# controller_schematic.net
KiCad netlist of a schematic drawn in EasyEDA
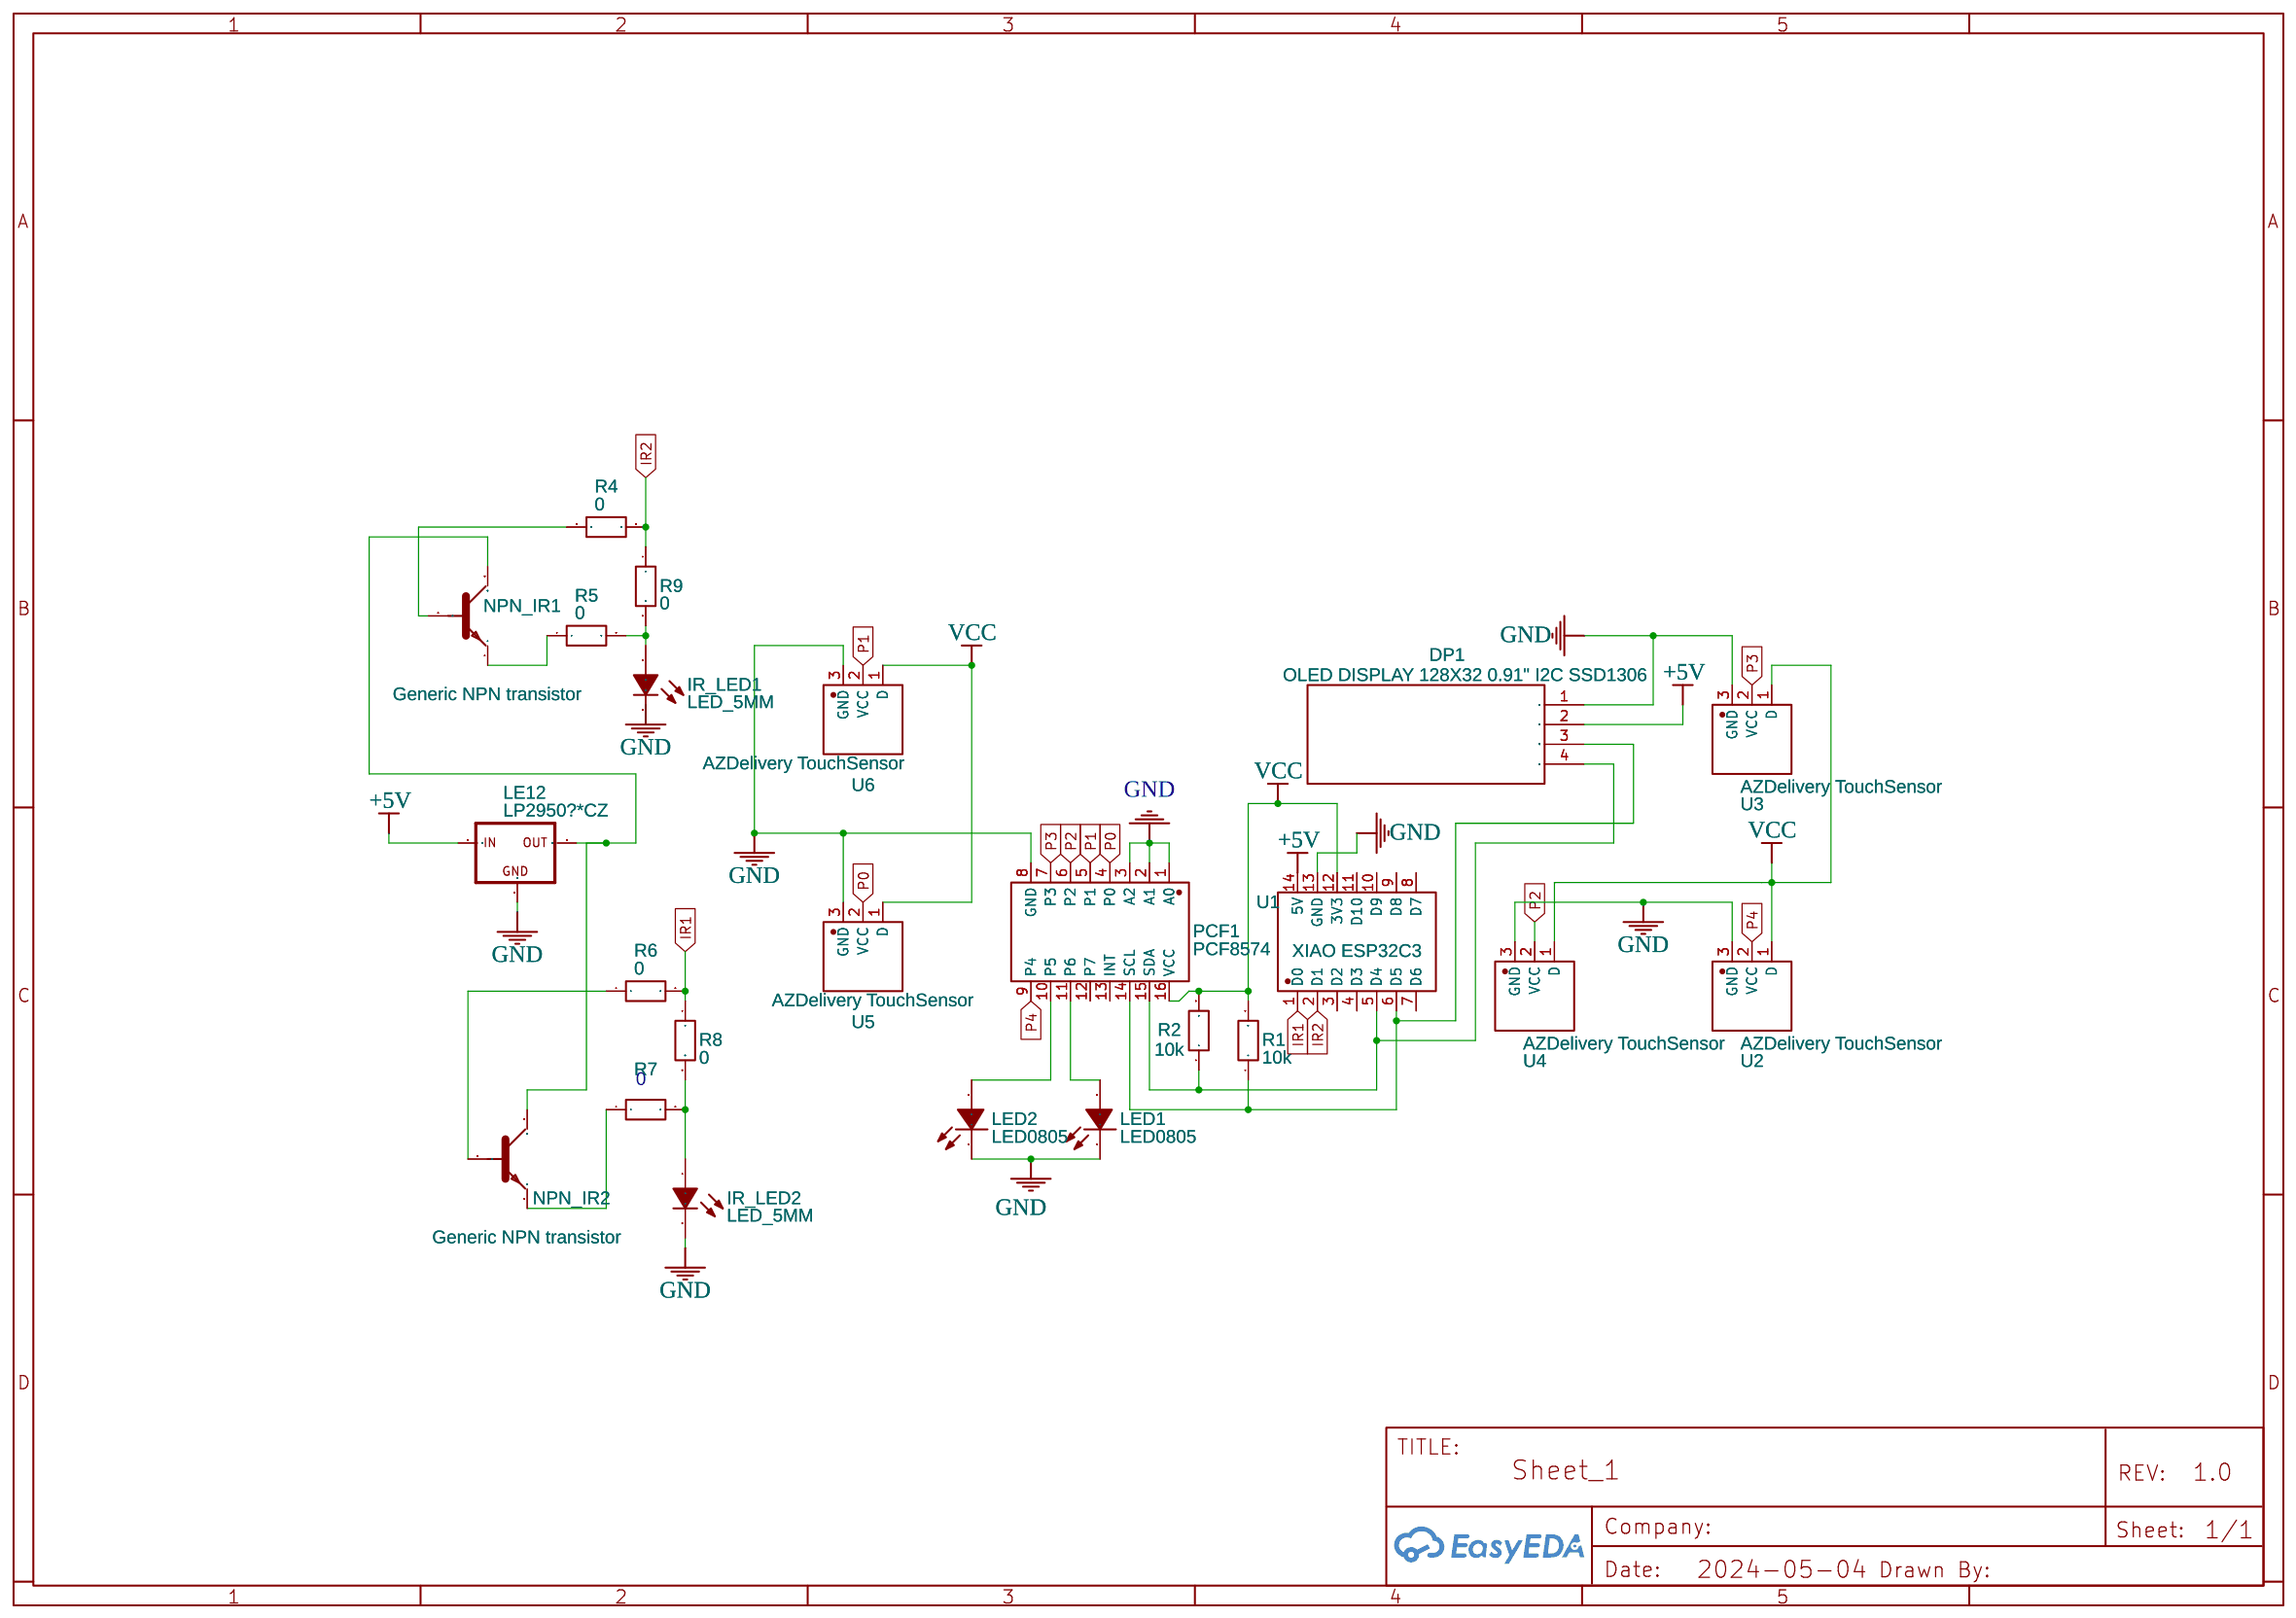
[diagram p0: schematic sheet]

(export (version "E")
  (design (tool "Eeschema 10.0.6"))
  (components
    (comp (ref "DP1")
      (value "OLED DISPLAY 128X32 0.91\" I2C SSD1306")
      (libsource (lib "") (part "OLED DISPLAY 128X32 0.91{dblquote} I2C SSD1306"))
    )
    (comp (ref "IR_LED1") (value "LED_5MM") (libsource (lib "") (part "LED_5MM")))
    (comp (ref "IR_LED2") (value "LED_5MM") (libsource (lib "") (part "LED_5MM")))
    (comp (ref "LE12") (value "LP2950?*CZ") (libsource (lib "") (part "LP2950?*CZ")))
    (comp (ref "LED1")
      (value "LED0805")
      (fields (field (name "Manufacturer Part") "led0805"))
      (libsource (lib "") (part "LED0805"))
    )
    (comp (ref "LED2")
      (value "LED0805")
      (fields (field (name "Manufacturer Part") "led0805"))
      (libsource (lib "") (part "LED0805"))
    )
    (comp (ref "NPN_IR1")
      (value "Generic NPN transistor")
      (fields
        (field (name "Manufacturer Part") "PN2484 PBFREE")
        (field (name "Manufacturer") "Central Semiconductor")
      )
      (libsource (lib "") (part "Generic NPN transistor"))
    )
    (comp (ref "NPN_IR2")
      (value "Generic NPN transistor")
      (fields
        (field (name "Manufacturer Part") "PN2484 PBFREE")
        (field (name "Manufacturer") "Central Semiconductor")
      )
      (libsource (lib "") (part "Generic NPN transistor"))
    )
    (comp (ref "PCF1") (value "PCF8574") (libsource (lib "") (part "PCF8574")))
    (comp (ref "R1") (value "10k") (libsource (lib "") (part "R_0603_EU")))
    (comp (ref "R2") (value "10k") (libsource (lib "") (part "R_0603_EU")))
    (comp (ref "R4") (value "0") (libsource (lib "") (part "R_0603_EU_1")))
    (comp (ref "R5") (value "0") (libsource (lib "") (part "R_0603_EU_1")))
    (comp (ref "R6") (value "0") (libsource (lib "") (part "R_0603_EU_1")))
    (comp (ref "R7") (value "0") (libsource (lib "") (part "R_0603_EU_1")))
    (comp (ref "R8") (value "0") (libsource (lib "") (part "R_0603_EU_2")))
    (comp (ref "R9") (value "0") (libsource (lib "") (part "R_0603_EU_2")))
    (comp (ref "U1") (value "XIAO ESP32C3") (libsource (lib "") (part "XIAO ESP32C3")))
    (comp (ref "U2")
      (value "AZDelivery TouchSensor")
      (fields
        (field (name "Manufacturer Part") "ZJY096S0700BG01蓝色")
        (field (name "Manufacturer") "AZDelivery")
      )
      (libsource (lib "") (part "AZDelivery TouchSensor"))
    )
    (comp (ref "U3")
      (value "AZDelivery TouchSensor")
      (fields
        (field (name "Manufacturer Part") "ZJY096S0700BG01蓝色")
        (field (name "Manufacturer") "AZDelivery")
      )
      (libsource (lib "") (part "AZDelivery TouchSensor"))
    )
    (comp (ref "U4")
      (value "AZDelivery TouchSensor")
      (fields
        (field (name "Manufacturer Part") "ZJY096S0700BG01蓝色")
        (field (name "Manufacturer") "AZDelivery")
      )
      (libsource (lib "") (part "AZDelivery TouchSensor"))
    )
    (comp (ref "U5")
      (value "AZDelivery TouchSensor")
      (fields
        (field (name "Manufacturer Part") "ZJY096S0700BG01蓝色")
        (field (name "Manufacturer") "AZDelivery")
      )
      (libsource (lib "") (part "AZDelivery TouchSensor"))
    )
    (comp (ref "U6")
      (value "AZDelivery TouchSensor")
      (fields
        (field (name "Manufacturer Part") "ZJY096S0700BG01蓝色")
        (field (name "Manufacturer") "AZDelivery")
      )
      (libsource (lib "") (part "AZDelivery TouchSensor"))
    )
  )
  (nets
    (net (code "1") (name "+5V") (class "Default")
      (node (ref "DP1") (pin "2") (pinfunction "VCC_2") (pintype "passive"))
      (node (ref "LE12") (pin "3") (pinfunction "IN_3") (pintype "bidirectional"))
      (node (ref "U1") (pin "14") (pinfunction "5V_14") (pintype "unspecified"))
    )
    (net (code "2") (name "GND") (class "Default")
      (node (ref "DP1") (pin "1") (pinfunction "GND_1") (pintype "passive"))
      (node (ref "IR_LED1") (pin "2") (pinfunction "K_2") (pintype "input"))
      (node (ref "IR_LED2") (pin "2") (pinfunction "K_2") (pintype "input"))
      (node (ref "LE12") (pin "2") (pinfunction "GND_2") (pintype "bidirectional"))
      (node (ref "LED1") (pin "1") (pinfunction "-_1") (pintype "unspecified"))
      (node (ref "LED2") (pin "1") (pinfunction "-_1") (pintype "unspecified"))
      (node (ref "PCF1") (pin "1") (pinfunction "A0_1") (pintype "unspecified"))
      (node (ref "PCF1") (pin "2") (pinfunction "A1_2") (pintype "unspecified"))
      (node (ref "PCF1") (pin "3") (pinfunction "A2_3") (pintype "unspecified"))
      (node (ref "PCF1") (pin "8") (pinfunction "GND_8") (pintype "unspecified"))
      (node (ref "U1") (pin "13") (pinfunction "GND_13") (pintype "unspecified"))
      (node (ref "U2") (pin "3") (pinfunction "GND_3") (pintype "unspecified"))
      (node (ref "U3") (pin "3") (pinfunction "GND_3") (pintype "unspecified"))
      (node (ref "U4") (pin "3") (pinfunction "GND_3") (pintype "unspecified"))
      (node (ref "U5") (pin "3") (pinfunction "GND_3") (pintype "unspecified"))
      (node (ref "U6") (pin "3") (pinfunction "GND_3") (pintype "unspecified"))
    )
    (net (code "3") (name "IR1") (class "Default")
      (node (ref "R6") (pin "2") (pinfunction "2_2") (pintype "unspecified"))
      (node (ref "R8") (pin "1") (pinfunction "1_1") (pintype "unspecified"))
      (node (ref "U1") (pin "1") (pinfunction "D0_1") (pintype "unspecified"))
    )
    (net (code "4") (name "IR2") (class "Default")
      (node (ref "R4") (pin "2") (pinfunction "2_2") (pintype "unspecified"))
      (node (ref "R9") (pin "1") (pinfunction "1_1") (pintype "unspecified"))
      (node (ref "U1") (pin "2") (pinfunction "D1_2") (pintype "unspecified"))
    )
    (net (code "5") (name "Net-(DP1-SCL)") (class "Default")
      (node (ref "DP1") (pin "3") (pinfunction "SCL_3") (pintype "input"))
      (node (ref "PCF1") (pin "14") (pinfunction "SCL_14") (pintype "unspecified"))
      (node (ref "R1") (pin "1") (pinfunction "1_1") (pintype "unspecified"))
      (node (ref "U1") (pin "6") (pinfunction "D5_6") (pintype "unspecified"))
    )
    (net (code "6") (name "Net-(DP1-SDA)") (class "Default")
      (node (ref "DP1") (pin "4") (pinfunction "SDA_4") (pintype "input"))
      (node (ref "PCF1") (pin "15") (pinfunction "SDA_15") (pintype "unspecified"))
      (node (ref "R2") (pin "1") (pinfunction "1_1") (pintype "unspecified"))
      (node (ref "U1") (pin "5") (pinfunction "D4_5") (pintype "unspecified"))
    )
    (net (code "7") (name "Net-(IR_LED1-A)") (class "Default")
      (node (ref "IR_LED1") (pin "1") (pinfunction "A_1") (pintype "input"))
      (node (ref "R5") (pin "2") (pinfunction "2_2") (pintype "unspecified"))
      (node (ref "R9") (pin "2") (pinfunction "2_2") (pintype "unspecified"))
    )
    (net (code "8") (name "Net-(IR_LED2-A)") (class "Default")
      (node (ref "IR_LED2") (pin "1") (pinfunction "A_1") (pintype "input"))
      (node (ref "R7") (pin "2") (pinfunction "2_2") (pintype "unspecified"))
      (node (ref "R8") (pin "2") (pinfunction "2_2") (pintype "unspecified"))
    )
    (net (code "9") (name "Net-(LE12-OUT)") (class "Default")
      (node (ref "LE12") (pin "1") (pinfunction "OUT_1") (pintype "bidirectional"))
      (node (ref "NPN_IR1") (pin "3") (pinfunction "C_3") (pintype "bidirectional"))
      (node (ref "NPN_IR2") (pin "3") (pinfunction "C_3") (pintype "bidirectional"))
    )
    (net (code "10") (name "Net-(LED1-+)") (class "Default")
      (node (ref "LED1") (pin "2") (pinfunction "+_2") (pintype "unspecified"))
      (node (ref "PCF1") (pin "11") (pinfunction "P6_11") (pintype "unspecified"))
    )
    (net (code "11") (name "Net-(LED2-+)") (class "Default")
      (node (ref "LED2") (pin "2") (pinfunction "+_2") (pintype "unspecified"))
      (node (ref "PCF1") (pin "10") (pinfunction "P5_10") (pintype "unspecified"))
    )
    (net (code "12") (name "Net-(NPN_IR1-B)") (class "Default")
      (node (ref "NPN_IR1") (pin "2") (pinfunction "B_2") (pintype "bidirectional"))
      (node (ref "R4") (pin "1") (pinfunction "1_1") (pintype "unspecified"))
    )
    (net (code "13") (name "Net-(NPN_IR1-E)") (class "Default")
      (node (ref "NPN_IR1") (pin "1") (pinfunction "E_1") (pintype "bidirectional"))
      (node (ref "R5") (pin "1") (pinfunction "1_1") (pintype "unspecified"))
    )
    (net (code "14") (name "Net-(NPN_IR2-B)") (class "Default")
      (node (ref "NPN_IR2") (pin "2") (pinfunction "B_2") (pintype "bidirectional"))
      (node (ref "R6") (pin "1") (pinfunction "1_1") (pintype "unspecified"))
    )
    (net (code "15") (name "Net-(NPN_IR2-E)") (class "Default")
      (node (ref "NPN_IR2") (pin "1") (pinfunction "E_1") (pintype "bidirectional"))
      (node (ref "R7") (pin "1") (pinfunction "1_1") (pintype "unspecified"))
    )
    (net (code "16") (name "P0") (class "Default")
      (node (ref "PCF1") (pin "4") (pinfunction "P0_4") (pintype "unspecified"))
      (node (ref "U5") (pin "2") (pinfunction "VCC_2") (pintype "unspecified"))
    )
    (net (code "17") (name "P1") (class "Default")
      (node (ref "PCF1") (pin "5") (pinfunction "P1_5") (pintype "unspecified"))
      (node (ref "U6") (pin "2") (pinfunction "VCC_2") (pintype "unspecified"))
    )
    (net (code "18") (name "P2") (class "Default")
      (node (ref "PCF1") (pin "6") (pinfunction "P2_6") (pintype "unspecified"))
      (node (ref "U4") (pin "2") (pinfunction "VCC_2") (pintype "unspecified"))
    )
    (net (code "19") (name "P3") (class "Default")
      (node (ref "PCF1") (pin "7") (pinfunction "P3_7") (pintype "unspecified"))
      (node (ref "U3") (pin "2") (pinfunction "VCC_2") (pintype "unspecified"))
    )
    (net (code "20") (name "P4") (class "Default")
      (node (ref "PCF1") (pin "9") (pinfunction "P4_9") (pintype "unspecified"))
      (node (ref "U2") (pin "2") (pinfunction "VCC_2") (pintype "unspecified"))
    )
    (net (code "21") (name "VCC") (class "Default")
      (node (ref "PCF1") (pin "16") (pinfunction "VCC_16") (pintype "unspecified"))
      (node (ref "R1") (pin "2") (pinfunction "2_2") (pintype "unspecified"))
      (node (ref "R2") (pin "2") (pinfunction "2_2") (pintype "unspecified"))
      (node (ref "U1") (pin "12") (pinfunction "3V3_12") (pintype "unspecified"))
      (node (ref "U2") (pin "1") (pinfunction "D_1") (pintype "unspecified"))
      (node (ref "U3") (pin "1") (pinfunction "D_1") (pintype "unspecified"))
      (node (ref "U4") (pin "1") (pinfunction "D_1") (pintype "unspecified"))
      (node (ref "U5") (pin "1") (pinfunction "D_1") (pintype "unspecified"))
      (node (ref "U6") (pin "1") (pinfunction "D_1") (pintype "unspecified"))
    )
    (net (code "22") (name "unconnected-(PCF1-INT-Pad13)") (class "Default")
      (node (ref "PCF1") (pin "13") (pinfunction "INT_13") (pintype "unspecified"))
    )
    (net (code "23") (name "unconnected-(PCF1-P7-Pad12)") (class "Default")
      (node (ref "PCF1") (pin "12") (pinfunction "P7_12") (pintype "unspecified"))
    )
    (net (code "24") (name "unconnected-(U1-D2-Pad3)") (class "Default")
      (node (ref "U1") (pin "3") (pinfunction "D2_3") (pintype "unspecified"))
    )
    (net (code "25") (name "unconnected-(U1-D3-Pad4)") (class "Default")
      (node (ref "U1") (pin "4") (pinfunction "D3_4") (pintype "unspecified"))
    )
    (net (code "26") (name "unconnected-(U1-D6-Pad7)") (class "Default")
      (node (ref "U1") (pin "7") (pinfunction "D6_7") (pintype "unspecified"))
    )
    (net (code "27") (name "unconnected-(U1-D7-Pad8)") (class "Default")
      (node (ref "U1") (pin "8") (pinfunction "D7_8") (pintype "unspecified"))
    )
    (net (code "28") (name "unconnected-(U1-D8-Pad9)") (class "Default")
      (node (ref "U1") (pin "9") (pinfunction "D8_9") (pintype "unspecified"))
    )
    (net (code "29") (name "unconnected-(U1-D9-Pad10)") (class "Default")
      (node (ref "U1") (pin "10") (pinfunction "D9_10") (pintype "unspecified"))
    )
    (net (code "30") (name "unconnected-(U1-D10-Pad11)") (class "Default")
      (node (ref "U1") (pin "11") (pinfunction "D10_11") (pintype "unspecified"))
    )
  )
)
